# hall_mitsuba.net
KiCad netlist of a schematic drawn in EAGLE
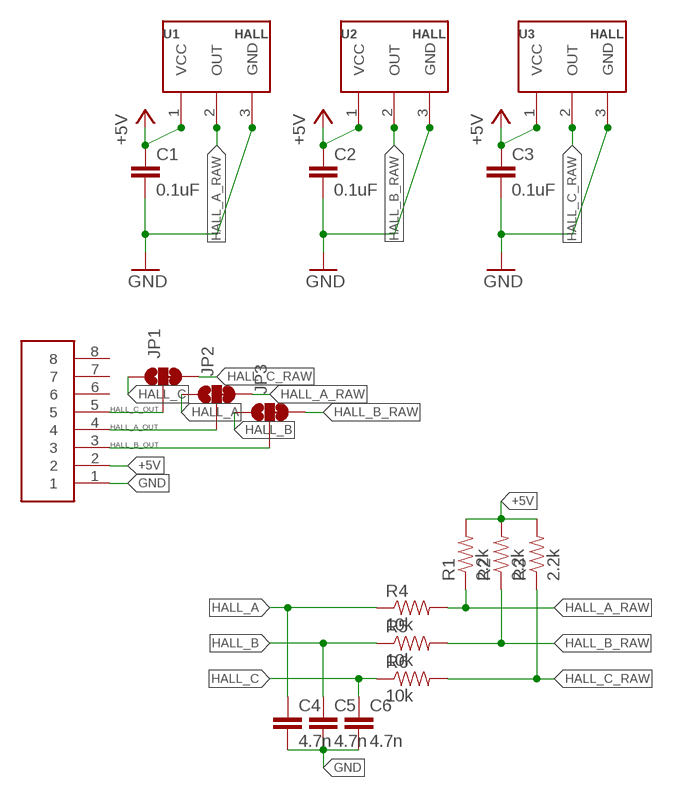
[diagram p0: schematic, sheet 1]

(export (version "E")
  (design (tool "Eeschema 10.0.6"))
  (components
    (comp (ref "C1")
      (value "0.1uF")
      (footprint "eagle-import:0603-CAP")
      (libsource (lib "eagle-import") (part "CAP0603-CAP"))
    )
    (comp (ref "C2")
      (value "0.1uF")
      (footprint "eagle-import:0603-CAP")
      (libsource (lib "eagle-import") (part "CAP0603-CAP"))
    )
    (comp (ref "C3")
      (value "0.1uF")
      (footprint "eagle-import:0603-CAP")
      (libsource (lib "eagle-import") (part "CAP0603-CAP"))
    )
    (comp (ref "C4")
      (value "4.7n")
      (footprint "eagle-import:0603-CAP")
      (libsource (lib "eagle-import") (part "CAP0603-CAP"))
    )
    (comp (ref "C5")
      (value "4.7n")
      (footprint "eagle-import:0603-CAP")
      (libsource (lib "eagle-import") (part "CAP0603-CAP"))
    )
    (comp (ref "C6")
      (value "4.7n")
      (footprint "eagle-import:0603-CAP")
      (libsource (lib "eagle-import") (part "CAP0603-CAP"))
    )
    (comp (ref "JP1")
      (value "JUMPER-SMT_3_1-NC_TRACE_SILK")
      (footprint "eagle-import:SMT-JUMPER_3_1-NC_TRACE_SILK")
      (libsource (lib "eagle-import") (part "JUMPER-SMT_3_1-NC_TRACE_SILK"))
    )
    (comp (ref "JP2")
      (value "JUMPER-SMT_3_1-NC_TRACE_SILK")
      (footprint "eagle-import:SMT-JUMPER_3_1-NC_TRACE_SILK")
      (libsource (lib "eagle-import") (part "JUMPER-SMT_3_1-NC_TRACE_SILK"))
    )
    (comp (ref "JP3")
      (value "JUMPER-SMT_3_1-NC_TRACE_SILK")
      (footprint "eagle-import:SMT-JUMPER_3_1-NC_TRACE_SILK")
      (libsource (lib "eagle-import") (part "JUMPER-SMT_3_1-NC_TRACE_SILK"))
    )
    (comp (ref "R1")
      (value "2.2k")
      (footprint "eagle-import:0603-RES")
      (libsource (lib "eagle-import") (part "RESISTOR0603-RES"))
    )
    (comp (ref "R2")
      (value "2.2k")
      (footprint "eagle-import:0603-RES")
      (libsource (lib "eagle-import") (part "RESISTOR0603-RES"))
    )
    (comp (ref "R3")
      (value "2.2k")
      (footprint "eagle-import:0603-RES")
      (libsource (lib "eagle-import") (part "RESISTOR0603-RES"))
    )
    (comp (ref "R4")
      (value "10k")
      (footprint "eagle-import:0603-RES")
      (libsource (lib "eagle-import") (part "RESISTOR0603-RES"))
    )
    (comp (ref "R5")
      (value "10k")
      (footprint "eagle-import:0603-RES")
      (libsource (lib "eagle-import") (part "RESISTOR0603-RES"))
    )
    (comp (ref "R6")
      (value "10k")
      (footprint "eagle-import:0603-RES")
      (libsource (lib "eagle-import") (part "RESISTOR0603-RES"))
    )
    (comp (ref "U$1")
      (value "HEADER8DEFAULT")
      (footprint "eagle-import:8PINVALULOK")
      (libsource (lib "eagle-import") (part "HEADER8DEFAULT"))
    )
    (comp (ref "U1")
      (value "HALL_SOT23W")
      (footprint "eagle-import:SOT23W")
      (libsource (lib "eagle-import") (part "HALL_SOT23W"))
    )
    (comp (ref "U2")
      (value "HALL_SOT23W")
      (footprint "eagle-import:SOT23W")
      (libsource (lib "eagle-import") (part "HALL_SOT23W"))
    )
    (comp (ref "U3")
      (value "HALL_SOT23W")
      (footprint "eagle-import:SOT23W")
      (libsource (lib "eagle-import") (part "HALL_SOT23W"))
    )
  )
  (nets
    (net (code "1") (name "+5V") (class "Default")
      (node (ref "C1") (pin "1") (pinfunction "1_1") (pintype "passive"))
      (node (ref "C2") (pin "1") (pinfunction "1_1") (pintype "passive"))
      (node (ref "C3") (pin "1") (pinfunction "1_1") (pintype "passive"))
      (node (ref "R1") (pin "2") (pinfunction "2_2") (pintype "passive"))
      (node (ref "R2") (pin "2") (pinfunction "2_2") (pintype "passive"))
      (node (ref "R3") (pin "2") (pinfunction "2_2") (pintype "passive"))
      (node (ref "U$1") (pin "2") (pinfunction "2_2") (pintype "bidirectional"))
      (node (ref "U1") (pin "1") (pinfunction "VCC_1") (pintype "bidirectional"))
      (node (ref "U2") (pin "1") (pinfunction "VCC_1") (pintype "bidirectional"))
      (node (ref "U3") (pin "1") (pinfunction "VCC_1") (pintype "bidirectional"))
    )
    (net (code "2") (name "/HALL_A_OUT") (class "Default")
      (node (ref "JP2") (pin "2") (pinfunction "2_2") (pintype "passive"))
      (node (ref "U$1") (pin "4") (pinfunction "4_4") (pintype "bidirectional"))
    )
    (net (code "3") (name "/HALL_B_OUT") (class "Default")
      (node (ref "JP3") (pin "2") (pinfunction "2_2") (pintype "passive"))
      (node (ref "U$1") (pin "3") (pinfunction "3_3") (pintype "bidirectional"))
    )
    (net (code "4") (name "/HALL_C_OUT") (class "Default")
      (node (ref "JP1") (pin "2") (pinfunction "2_2") (pintype "passive"))
      (node (ref "U$1") (pin "5") (pinfunction "5_5") (pintype "bidirectional"))
    )
    (net (code "5") (name "GND") (class "Default")
      (node (ref "C1") (pin "2") (pinfunction "2_2") (pintype "passive"))
      (node (ref "C2") (pin "2") (pinfunction "2_2") (pintype "passive"))
      (node (ref "C3") (pin "2") (pinfunction "2_2") (pintype "passive"))
      (node (ref "C4") (pin "2") (pinfunction "2_2") (pintype "passive"))
      (node (ref "C5") (pin "2") (pinfunction "2_2") (pintype "passive"))
      (node (ref "C6") (pin "2") (pinfunction "2_2") (pintype "passive"))
      (node (ref "U$1") (pin "1") (pinfunction "1_1") (pintype "bidirectional"))
      (node (ref "U1") (pin "3") (pinfunction "GND_3") (pintype "bidirectional"))
      (node (ref "U2") (pin "3") (pinfunction "GND_3") (pintype "bidirectional"))
      (node (ref "U3") (pin "3") (pinfunction "GND_3") (pintype "bidirectional"))
    )
    (net (code "6") (name "HALL_A") (class "Default")
      (node (ref "C4") (pin "1") (pinfunction "1_1") (pintype "passive"))
      (node (ref "JP2") (pin "1") (pinfunction "1_1") (pintype "passive"))
      (node (ref "R4") (pin "1") (pinfunction "1_1") (pintype "passive"))
    )
    (net (code "7") (name "HALL_A_RAW") (class "Default")
      (node (ref "JP2") (pin "3") (pinfunction "3_3") (pintype "passive"))
      (node (ref "R1") (pin "1") (pinfunction "1_1") (pintype "passive"))
      (node (ref "R4") (pin "2") (pinfunction "2_2") (pintype "passive"))
      (node (ref "U1") (pin "2") (pinfunction "OUT_2") (pintype "bidirectional"))
    )
    (net (code "8") (name "HALL_B") (class "Default")
      (node (ref "C5") (pin "1") (pinfunction "1_1") (pintype "passive"))
      (node (ref "JP3") (pin "1") (pinfunction "1_1") (pintype "passive"))
      (node (ref "R5") (pin "1") (pinfunction "1_1") (pintype "passive"))
    )
    (net (code "9") (name "HALL_B_RAW") (class "Default")
      (node (ref "JP3") (pin "3") (pinfunction "3_3") (pintype "passive"))
      (node (ref "R2") (pin "1") (pinfunction "1_1") (pintype "passive"))
      (node (ref "R5") (pin "2") (pinfunction "2_2") (pintype "passive"))
      (node (ref "U2") (pin "2") (pinfunction "OUT_2") (pintype "bidirectional"))
    )
    (net (code "10") (name "HALL_C") (class "Default")
      (node (ref "C6") (pin "1") (pinfunction "1_1") (pintype "passive"))
      (node (ref "JP1") (pin "1") (pinfunction "1_1") (pintype "passive"))
      (node (ref "R6") (pin "1") (pinfunction "1_1") (pintype "passive"))
    )
    (net (code "11") (name "HALL_C_RAW") (class "Default")
      (node (ref "JP1") (pin "3") (pinfunction "3_3") (pintype "passive"))
      (node (ref "R3") (pin "1") (pinfunction "1_1") (pintype "passive"))
      (node (ref "R6") (pin "2") (pinfunction "2_2") (pintype "passive"))
      (node (ref "U3") (pin "2") (pinfunction "OUT_2") (pintype "bidirectional"))
    )
    (net (code "12") (name "unconnected-(U$1-Pad6)") (class "Default")
      (node (ref "U$1") (pin "6") (pinfunction "6_6") (pintype "bidirectional"))
    )
    (net (code "13") (name "unconnected-(U$1-Pad7)") (class "Default")
      (node (ref "U$1") (pin "7") (pinfunction "7_7") (pintype "bidirectional"))
    )
    (net (code "14") (name "unconnected-(U$1-Pad8)") (class "Default")
      (node (ref "U$1") (pin "8") (pinfunction "8_8") (pintype "bidirectional"))
    )
  )
)
